# sensor_de_tension.net
KiCad netlist of a schematic drawn in Altium Designer
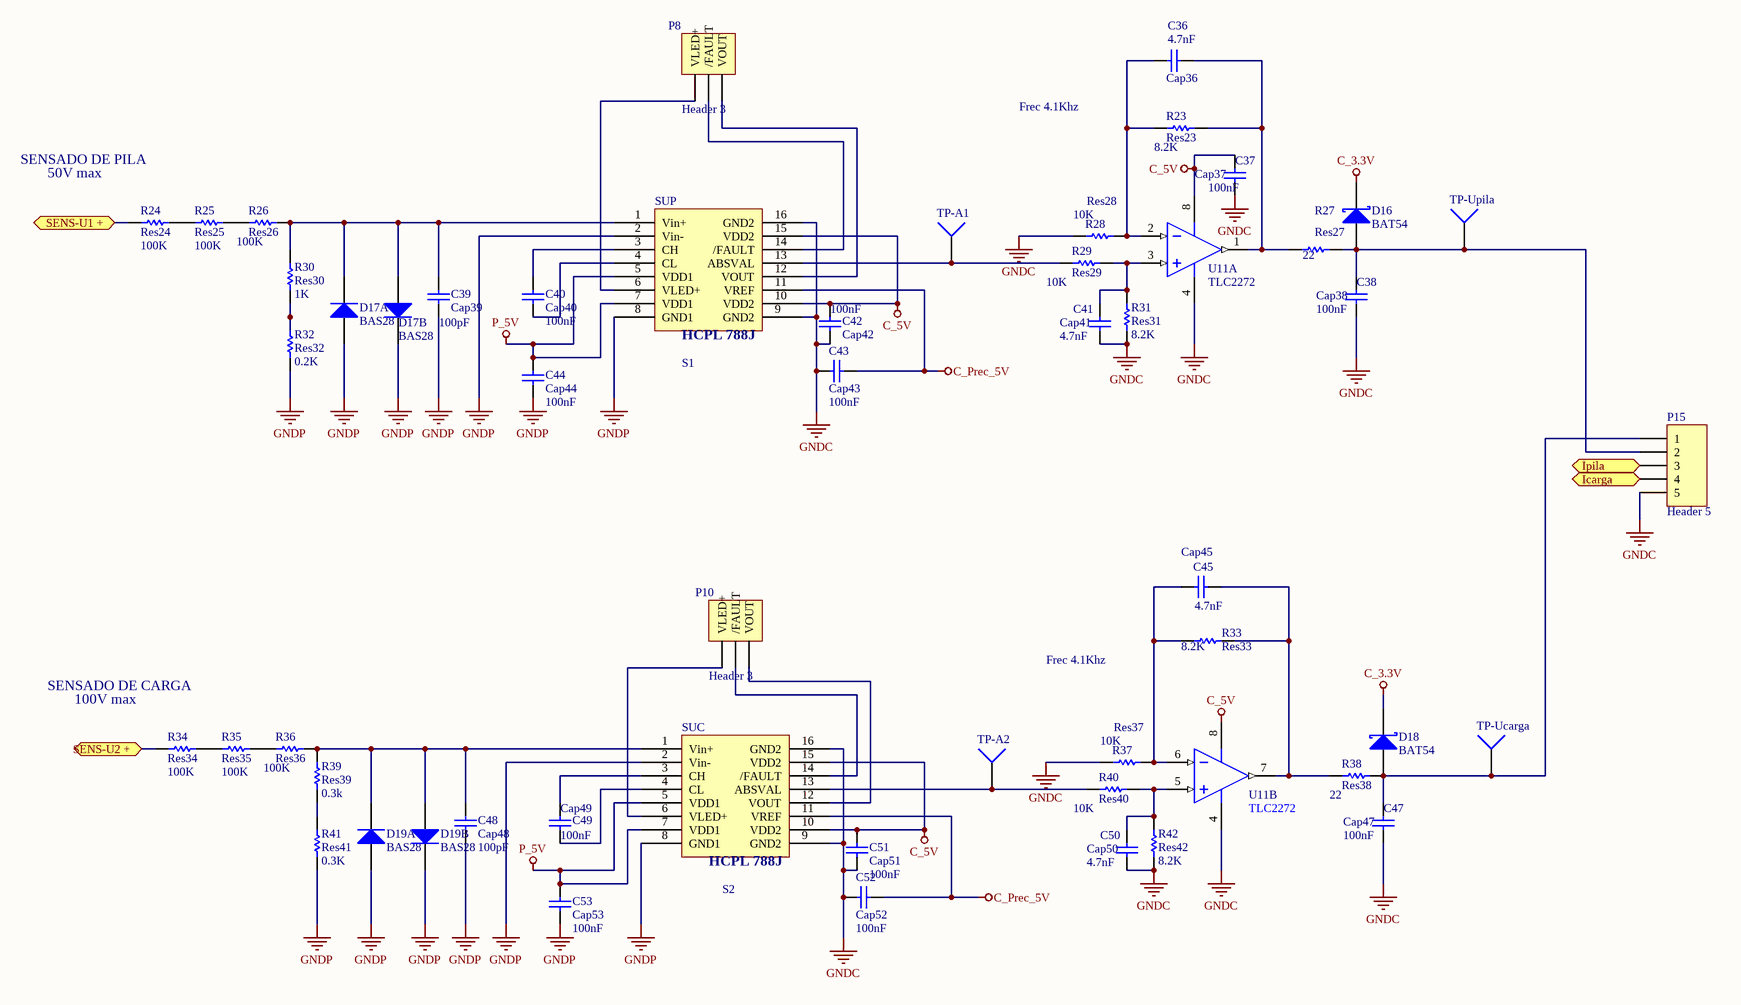
[diagram p0: sensor de tension.SchDoc]

(export (version "E")
  (design (tool "Eeschema 10.0.6"))
  (components
    (comp (ref "C36")
      (value "Cap36")
      (footprint "RAD-0.1")
      (description "THRU MULTICAPA 50V")
      (fields (field (name "ALTIUM_VALUE") "4.7nF") (field (name "PUBLISHER") "Altium Limited"))
      (libsource (lib "Miscellaneous Devices") (part "Cap"))
    )
    (comp (ref "C37")
      (value "Cap37")
      (footprint "8-1206")
      (description "SMD MULTICAPA 50V")
      (fields (field (name "ALTIUM_VALUE") "100nF") (field (name "PUBLISHER") "Altium Limited"))
      (libsource (lib "Miscellaneous Devices") (part "Cap"))
    )
    (comp (ref "C38")
      (value "Cap38")
      (footprint "8-1206")
      (description "SMD MULTICAPA 50V")
      (fields (field (name "ALTIUM_VALUE") "100nF") (field (name "PUBLISHER") "Altium Limited"))
      (libsource (lib "Miscellaneous Devices") (part "Cap"))
    )
    (comp (ref "C39")
      (value "Cap39")
      (footprint "8-1206")
      (description "SMD MULTICAPA 50V")
      (fields (field (name "ALTIUM_VALUE") "100pF") (field (name "PUBLISHER") "Altium Limited"))
      (libsource (lib "Miscellaneous Devices") (part "Cap"))
    )
    (comp (ref "C40")
      (value "Cap40")
      (footprint "8-1206")
      (description "SMD MULTICAPA 50V")
      (fields (field (name "ALTIUM_VALUE") "100nF") (field (name "PUBLISHER") "Altium Limited"))
      (libsource (lib "Miscellaneous Devices") (part "Cap"))
    )
    (comp (ref "C41")
      (value "Cap41")
      (footprint "RAD-0.1")
      (description "THRU MULTICAPA 50V")
      (fields (field (name "ALTIUM_VALUE") "4.7nF") (field (name "PUBLISHER") "Altium Limited"))
      (libsource (lib "Miscellaneous Devices") (part "Cap"))
    )
    (comp (ref "C42")
      (value "Cap42")
      (footprint "8-1206")
      (description "SMD MULTICAPA 50V")
      (fields (field (name "ALTIUM_VALUE") "100nF") (field (name "PUBLISHER") "Altium Limited"))
      (libsource (lib "Miscellaneous Devices") (part "Cap"))
    )
    (comp (ref "C43")
      (value "Cap43")
      (footprint "8-1206")
      (description "SMD MULTICAPA 50V")
      (fields (field (name "ALTIUM_VALUE") "100nF") (field (name "PUBLISHER") "Altium Limited"))
      (libsource (lib "Miscellaneous Devices") (part "Cap"))
    )
    (comp (ref "C44")
      (value "Cap44")
      (footprint "8-1206")
      (description "SMD MULTICAPA 50V")
      (fields (field (name "ALTIUM_VALUE") "100nF") (field (name "PUBLISHER") "Altium Limited"))
      (libsource (lib "Miscellaneous Devices") (part "Cap"))
    )
    (comp (ref "C45")
      (value "Cap45")
      (footprint "RAD-0.1")
      (description "THRU MULTICAPA 50V")
      (fields (field (name "ALTIUM_VALUE") "4.7nF") (field (name "PUBLISHER") "Altium Limited"))
      (libsource (lib "Miscellaneous Devices") (part "Cap"))
    )
    (comp (ref "C47")
      (value "Cap47")
      (footprint "8-1206")
      (description "SMD MULTICAPA 50V")
      (fields (field (name "ALTIUM_VALUE") "100nF") (field (name "PUBLISHER") "Altium Limited"))
      (libsource (lib "Miscellaneous Devices") (part "Cap"))
    )
    (comp (ref "C48")
      (value "Cap48")
      (footprint "8-1206")
      (description "SMD MULTICAPA 50V")
      (fields (field (name "ALTIUM_VALUE") "100pF") (field (name "PUBLISHER") "Altium Limited"))
      (libsource (lib "Miscellaneous Devices") (part "Cap"))
    )
    (comp (ref "C49")
      (value "Cap49")
      (footprint "8-1206")
      (description "SMD MULTICAPA 50V")
      (fields (field (name "ALTIUM_VALUE") "100nF") (field (name "PUBLISHER") "Altium Limited"))
      (libsource (lib "Miscellaneous Devices") (part "Cap"))
    )
    (comp (ref "C50")
      (value "Cap50")
      (footprint "RAD-0.1")
      (description "THRU MULTICAPA 50V")
      (fields (field (name "ALTIUM_VALUE") "4.7nF") (field (name "PUBLISHER") "Altium Limited"))
      (libsource (lib "Miscellaneous Devices") (part "Cap"))
    )
    (comp (ref "C51")
      (value "Cap51")
      (footprint "8-1206")
      (description "SMD MULTICAPA 50V")
      (fields (field (name "ALTIUM_VALUE") "100nF") (field (name "PUBLISHER") "Altium Limited"))
      (libsource (lib "Miscellaneous Devices") (part "Cap"))
    )
    (comp (ref "C52")
      (value "Cap52")
      (footprint "8-1206")
      (description "SMD MULTICAPA 50V")
      (fields (field (name "ALTIUM_VALUE") "100nF") (field (name "PUBLISHER") "Altium Limited"))
      (libsource (lib "Miscellaneous Devices") (part "Cap"))
    )
    (comp (ref "C53")
      (value "Cap53")
      (footprint "8-1206")
      (description "SMD MULTICAPA 50V")
      (fields (field (name "ALTIUM_VALUE") "100nF") (field (name "PUBLISHER") "Altium Limited"))
      (libsource (lib "Miscellaneous Devices") (part "Cap"))
    )
    (comp (ref "D16")
      (value "BAT54")
      (footprint "SOD123*")
      (description "SMD")
      (fields (field (name "PUBLISHER") "Altium Limited"))
      (libsource (lib "Philips Discrete Diode - Schottky") (part "BAT54"))
    )
    (comp (ref "D17")
      (value "BAS28")
      (footprint "SOT-143*")
      (description "SMD")
      (fields (field (name "PUBLISHER") "Altium Limited"))
      (libsource (lib "Philips Discrete Diode - Switching") (part "BAS28"))
    )
    (comp (ref "D18")
      (value "BAT54")
      (footprint "SOD123*")
      (description "SMD")
      (fields (field (name "PUBLISHER") "Altium Limited"))
      (libsource (lib "Philips Discrete Diode - Schottky") (part "BAT54"))
    )
    (comp (ref "D19")
      (value "BAS28")
      (footprint "SOT-143*")
      (description "High-speed Switching, Double Diode SMD")
      (fields (field (name "PUBLISHER") "Altium Limited"))
      (libsource (lib "Philips Discrete Diode - Switching") (part "BAS28"))
    )
    (comp (ref "P8")
      (value "Header 3")
      (footprint "HDR1X3*")
      (description "Header, 3-Pin")
      (fields (field (name "PUBLISHER") "Altium Limited"))
      (libsource (lib "Miscellaneous Connectors") (part "Header 3"))
    )
    (comp (ref "P10")
      (value "Header 3")
      (footprint "HDR1X3*")
      (description "Header, 3-Pin")
      (fields (field (name "PUBLISHER") "Altium Limited"))
      (libsource (lib "Miscellaneous Connectors") (part "Header 3"))
    )
    (comp (ref "P15")
      (value "Header 5")
      (footprint "HDR1X5H*")
      (description "Header, 5-Pin")
      (fields (field (name "PUBLISHER") "Altium Limited"))
      (libsource (lib "Miscellaneous Connectors") (part "Header 5"))
    )
    (comp (ref "R23")
      (value "Res23")
      (footprint "AXIAL-0.4")
      (description "Resistor")
      (fields (field (name "ALTIUM_VALUE") "8.2K") (field (name "PUBLISHER") "Altium Limited"))
      (libsource (lib "Miscellaneous Devices") (part "Res1"))
    )
    (comp (ref "R24")
      (value "Res24")
      (footprint "8-1206")
      (description "SMD 1206")
      (fields (field (name "ALTIUM_VALUE") "100K") (field (name "PUBLISHER") "Altium Limited"))
      (libsource (lib "Miscellaneous Devices") (part "Res1"))
    )
    (comp (ref "R25")
      (value "Res25")
      (footprint "8-1206")
      (description "SMD 1206")
      (fields (field (name "ALTIUM_VALUE") "100K") (field (name "PUBLISHER") "Altium Limited"))
      (libsource (lib "Miscellaneous Devices") (part "Res1"))
    )
    (comp (ref "R26")
      (value "Res26")
      (footprint "8-1206")
      (description "SMD 1206")
      (fields (field (name "ALTIUM_VALUE") "100K") (field (name "PUBLISHER") "Altium Limited"))
      (libsource (lib "Miscellaneous Devices") (part "Res1"))
    )
    (comp (ref "R27")
      (value "Res27")
      (footprint "8-1206")
      (description "SMD 1206")
      (fields (field (name "ALTIUM_VALUE") "22") (field (name "PUBLISHER") "Altium Limited"))
      (libsource (lib "Miscellaneous Devices") (part "Res1"))
    )
    (comp (ref "R28")
      (value "Res28")
      (footprint "AXIAL-0.4")
      (description "Resistor")
      (fields (field (name "ALTIUM_VALUE") "10K") (field (name "PUBLISHER") "Altium Limited"))
      (libsource (lib "Miscellaneous Devices") (part "Res1"))
    )
    (comp (ref "R29")
      (value "Res29")
      (footprint "AXIAL-0.4")
      (description "Resistor")
      (fields (field (name "ALTIUM_VALUE") "10K") (field (name "PUBLISHER") "Altium Limited"))
      (libsource (lib "Miscellaneous Devices") (part "Res1"))
    )
    (comp (ref "R30")
      (value "Res30")
      (footprint "AXIAL-0.4")
      (description "Resistor")
      (fields (field (name "ALTIUM_VALUE") "1K") (field (name "PUBLISHER") "Altium Limited"))
      (libsource (lib "Miscellaneous Devices") (part "Res1"))
    )
    (comp (ref "R31")
      (value "Res31")
      (footprint "AXIAL-0.4")
      (description "Resistor")
      (fields (field (name "ALTIUM_VALUE") "8.2K") (field (name "PUBLISHER") "Altium Limited"))
      (libsource (lib "Miscellaneous Devices") (part "Res1"))
    )
    (comp (ref "R32")
      (value "Res32")
      (footprint "AXIAL-0.4")
      (description "Resistor")
      (fields (field (name "ALTIUM_VALUE") "0.2K") (field (name "PUBLISHER") "Altium Limited"))
      (libsource (lib "Miscellaneous Devices") (part "Res1"))
    )
    (comp (ref "R33")
      (value "Res33")
      (footprint "AXIAL-0.4")
      (description "Resistor")
      (fields (field (name "ALTIUM_VALUE") "8.2K") (field (name "PUBLISHER") "Altium Limited"))
      (libsource (lib "Miscellaneous Devices") (part "Res1"))
    )
    (comp (ref "R34")
      (value "Res34")
      (footprint "8-1206")
      (description "SMD 1206")
      (fields (field (name "ALTIUM_VALUE") "100K") (field (name "PUBLISHER") "Altium Limited"))
      (libsource (lib "Miscellaneous Devices") (part "Res1"))
    )
    (comp (ref "R35")
      (value "Res35")
      (footprint "8-1206")
      (description "SMD 1206")
      (fields (field (name "ALTIUM_VALUE") "100K") (field (name "PUBLISHER") "Altium Limited"))
      (libsource (lib "Miscellaneous Devices") (part "Res1"))
    )
    (comp (ref "R36")
      (value "Res36")
      (footprint "8-1206")
      (description "SMD 1206")
      (fields (field (name "ALTIUM_VALUE") "100K") (field (name "PUBLISHER") "Altium Limited"))
      (libsource (lib "Miscellaneous Devices") (part "Res1"))
    )
    (comp (ref "R37")
      (value "Res37")
      (footprint "AXIAL-0.4")
      (description "Resistor")
      (fields (field (name "ALTIUM_VALUE") "10K") (field (name "PUBLISHER") "Altium Limited"))
      (libsource (lib "Miscellaneous Devices") (part "Res1"))
    )
    (comp (ref "R38")
      (value "Res38")
      (footprint "8-1206")
      (description "SMD 1206")
      (fields (field (name "ALTIUM_VALUE") "22") (field (name "PUBLISHER") "Altium Limited"))
      (libsource (lib "Miscellaneous Devices") (part "Res1"))
    )
    (comp (ref "R39")
      (value "Res39")
      (footprint "AXIAL-0.4")
      (description "Resistor")
      (fields (field (name "ALTIUM_VALUE") "0.3k") (field (name "PUBLISHER") "Altium Limited"))
      (libsource (lib "Miscellaneous Devices") (part "Res1"))
    )
    (comp (ref "R40")
      (value "Res40")
      (footprint "AXIAL-0.4")
      (description "Resistor")
      (fields (field (name "ALTIUM_VALUE") "10K") (field (name "PUBLISHER") "Altium Limited"))
      (libsource (lib "Miscellaneous Devices") (part "Res1"))
    )
    (comp (ref "R41")
      (value "Res41")
      (footprint "AXIAL-0.4")
      (description "Resistor")
      (fields (field (name "ALTIUM_VALUE") "0.3K") (field (name "PUBLISHER") "Altium Limited"))
      (libsource (lib "Miscellaneous Devices") (part "Res1"))
    )
    (comp (ref "R42")
      (value "Res42")
      (footprint "AXIAL-0.4")
      (description "Resistor")
      (fields (field (name "ALTIUM_VALUE") "8.2K") (field (name "PUBLISHER") "Altium Limited"))
      (libsource (lib "Miscellaneous Devices") (part "Res1"))
    )
    (comp (ref "SUC")
      (value "S2")
      (footprint "Sens Tension HCPL-788J")
      (libsource (lib "sensor tension HCPL 788J") (part "Component_1"))
    )
    (comp (ref "SUP")
      (value "S1")
      (footprint "Sens Tension HCPL-788J")
      (libsource (lib "sensor tension HCPL 788J") (part "Component_1"))
    )
    (comp (ref "TP-A1")
      (value "~")
      (footprint "PIN1")
      (description "Socket")
      (fields (field (name "PUBLISHER") "Altium Limited"))
      (libsource (lib "Miscellaneous Connectors") (part "Socket"))
    )
    (comp (ref "TP-A2")
      (value "~")
      (footprint "PIN1")
      (description "Socket")
      (fields (field (name "PUBLISHER") "Altium Limited"))
      (libsource (lib "Miscellaneous Connectors") (part "Socket"))
    )
    (comp (ref "TP-Ucarga")
      (value "~")
      (footprint "PIN1")
      (description "Socket")
      (fields (field (name "PUBLISHER") "Altium Limited"))
      (libsource (lib "Miscellaneous Connectors") (part "Socket"))
    )
    (comp (ref "TP-Upila")
      (value "~")
      (footprint "PIN1")
      (description "Socket")
      (fields (field (name "PUBLISHER") "Altium Limited"))
      (libsource (lib "Miscellaneous Connectors") (part "Socket"))
    )
    (comp (ref "U11")
      (value "TLC2272")
      (footprint "751-02_N")
      (description "LinCMOS Precision Dual Operational Amplifier")
      (fields (field (name "PUBLISHER") "Altium Limited"))
      (libsource (lib "TI Operational Amplifier") (part "TLC27L2ACDR"))
    )
  )
  (nets
    (net (code "1") (name "/Icarga") (class "Default")
      (node (ref "P15") (pin "4") (pinfunction "4_4") (pintype "passive"))
    )
    (net (code "2") (name "/Ipila") (class "Default")
      (node (ref "P15") (pin "3") (pinfunction "3_3") (pintype "passive"))
    )
    (net (code "3") (name "/SENS-U1 +") (class "Default")
      (node (ref "R24") (pin "1") (pinfunction "1_1") (pintype "passive"))
    )
    (net (code "4") (name "/SENS-U2 +") (class "Default")
      (node (ref "R34") (pin "1") (pinfunction "1_1") (pintype "passive"))
    )
    (net (code "5") (name "C_3.3V") (class "Default")
      (node (ref "D16") (pin "2") (pinfunction "K_2") (pintype "passive"))
      (node (ref "D18") (pin "2") (pinfunction "K_2") (pintype "passive"))
    )
    (net (code "6") (name "C_5V") (class "Default")
      (node (ref "C37") (pin "1") (pinfunction "1_1") (pintype "passive"))
      (node (ref "C42") (pin "2") (pinfunction "2_2") (pintype "passive"))
      (node (ref "C51") (pin "2") (pinfunction "2_2") (pintype "passive"))
      (node (ref "SUC") (pin "10") (pinfunction "VDD2_10") (pintype "passive"))
      (node (ref "SUC") (pin "15") (pinfunction "VDD2_15") (pintype "passive"))
      (node (ref "SUP") (pin "10") (pinfunction "VDD2_10") (pintype "passive"))
      (node (ref "SUP") (pin "15") (pinfunction "VDD2_15") (pintype "passive"))
      (node (ref "U11") (pin "8") (pinfunction "VDD_8") (pintype "power_in"))
    )
    (net (code "7") (name "C_Prec_5V") (class "Default")
      (node (ref "C43") (pin "2") (pinfunction "2_2") (pintype "passive"))
      (node (ref "C52") (pin "2") (pinfunction "2_2") (pintype "passive"))
      (node (ref "SUC") (pin "11") (pinfunction "VREF_11") (pintype "passive"))
      (node (ref "SUP") (pin "11") (pinfunction "VREF_11") (pintype "passive"))
    )
    (net (code "8") (name "GNDC") (class "Default")
      (node (ref "C37") (pin "2") (pinfunction "2_2") (pintype "passive"))
      (node (ref "C38") (pin "2") (pinfunction "2_2") (pintype "passive"))
      (node (ref "C41") (pin "2") (pinfunction "2_2") (pintype "passive"))
      (node (ref "C42") (pin "1") (pinfunction "1_1") (pintype "passive"))
      (node (ref "C43") (pin "1") (pinfunction "1_1") (pintype "passive"))
      (node (ref "C47") (pin "2") (pinfunction "2_2") (pintype "passive"))
      (node (ref "C50") (pin "2") (pinfunction "2_2") (pintype "passive"))
      (node (ref "C51") (pin "1") (pinfunction "1_1") (pintype "passive"))
      (node (ref "C52") (pin "1") (pinfunction "1_1") (pintype "passive"))
      (node (ref "P15") (pin "5") (pinfunction "5_5") (pintype "passive"))
      (node (ref "R28") (pin "1") (pinfunction "1_1") (pintype "passive"))
      (node (ref "R31") (pin "2") (pinfunction "2_2") (pintype "passive"))
      (node (ref "R37") (pin "1") (pinfunction "1_1") (pintype "passive"))
      (node (ref "R42") (pin "2") (pinfunction "2_2") (pintype "passive"))
      (node (ref "SUC") (pin "16") (pinfunction "GND2_16") (pintype "passive"))
      (node (ref "SUC") (pin "9") (pinfunction "GND2_9") (pintype "passive"))
      (node (ref "SUP") (pin "16") (pinfunction "GND2_16") (pintype "passive"))
      (node (ref "SUP") (pin "9") (pinfunction "GND2_9") (pintype "passive"))
      (node (ref "U11") (pin "4") (pinfunction "GND_4") (pintype "power_in"))
    )
    (net (code "9") (name "GNDP") (class "Default")
      (node (ref "C39") (pin "2") (pinfunction "2_2") (pintype "passive"))
      (node (ref "C44") (pin "2") (pinfunction "2_2") (pintype "passive"))
      (node (ref "C48") (pin "2") (pinfunction "2_2") (pintype "passive"))
      (node (ref "C53") (pin "2") (pinfunction "2_2") (pintype "passive"))
      (node (ref "D17") (pin "2") (pinfunction "K_2") (pintype "passive"))
      (node (ref "D17") (pin "4") (pinfunction "A_4") (pintype "passive"))
      (node (ref "D19") (pin "2") (pinfunction "K_2") (pintype "passive"))
      (node (ref "D19") (pin "4") (pinfunction "A_4") (pintype "passive"))
      (node (ref "R32") (pin "2") (pinfunction "2_2") (pintype "passive"))
      (node (ref "R41") (pin "2") (pinfunction "2_2") (pintype "passive"))
      (node (ref "SUC") (pin "2") (pinfunction "Vin-_2") (pintype "passive"))
      (node (ref "SUC") (pin "8") (pinfunction "GND1_8") (pintype "passive"))
      (node (ref "SUP") (pin "2") (pinfunction "Vin-_2") (pintype "passive"))
      (node (ref "SUP") (pin "8") (pinfunction "GND1_8") (pintype "passive"))
    )
    (net (code "10") (name "Net-(D16-A)") (class "Default")
      (node (ref "C38") (pin "1") (pinfunction "1_1") (pintype "passive"))
      (node (ref "D16") (pin "1") (pinfunction "A_1") (pintype "passive"))
      (node (ref "P15") (pin "2") (pinfunction "2_2") (pintype "passive"))
      (node (ref "R27") (pin "2") (pinfunction "2_2") (pintype "passive"))
      (node (ref "TP-Upila") (pin "1") (pinfunction "1_1") (pintype "passive"))
    )
    (net (code "11") (name "Net-(D17A-K)") (class "Default")
      (node (ref "C39") (pin "1") (pinfunction "1_1") (pintype "passive"))
      (node (ref "D17") (pin "1") (pinfunction "K_1") (pintype "passive"))
      (node (ref "D17") (pin "3") (pinfunction "A_3") (pintype "passive"))
      (node (ref "R26") (pin "2") (pinfunction "2_2") (pintype "passive"))
      (node (ref "R30") (pin "1") (pinfunction "1_1") (pintype "passive"))
      (node (ref "SUP") (pin "1") (pinfunction "Vin+_1") (pintype "passive"))
    )
    (net (code "12") (name "Net-(D18-A)") (class "Default")
      (node (ref "C47") (pin "1") (pinfunction "1_1") (pintype "passive"))
      (node (ref "D18") (pin "1") (pinfunction "A_1") (pintype "passive"))
      (node (ref "P15") (pin "1") (pinfunction "1_1") (pintype "passive"))
      (node (ref "R38") (pin "2") (pinfunction "2_2") (pintype "passive"))
      (node (ref "TP-Ucarga") (pin "1") (pinfunction "1_1") (pintype "passive"))
    )
    (net (code "13") (name "Net-(D19A-K)") (class "Default")
      (node (ref "C48") (pin "1") (pinfunction "1_1") (pintype "passive"))
      (node (ref "D19") (pin "1") (pinfunction "K_1") (pintype "passive"))
      (node (ref "D19") (pin "3") (pinfunction "A_3") (pintype "passive"))
      (node (ref "R36") (pin "2") (pinfunction "2_2") (pintype "passive"))
      (node (ref "R39") (pin "1") (pinfunction "1_1") (pintype "passive"))
      (node (ref "SUC") (pin "1") (pinfunction "Vin+_1") (pintype "passive"))
    )
    (net (code "14") (name "Net-(P8-VLED+)") (class "Default")
      (node (ref "P8") (pin "1") (pinfunction "VLED+_1") (pintype "passive"))
      (node (ref "SUP") (pin "6") (pinfunction "VLED+_6") (pintype "passive"))
    )
    (net (code "15") (name "Net-(P8-VOUT)") (class "Default")
      (node (ref "P8") (pin "3") (pinfunction "VOUT_3") (pintype "passive"))
      (node (ref "SUP") (pin "12") (pinfunction "VOUT_12") (pintype "passive"))
    )
    (net (code "16") (name "Net-(P8-{slash}FAULT)") (class "Default")
      (node (ref "P8") (pin "2") (pinfunction "/FAULT_2") (pintype "passive"))
      (node (ref "SUP") (pin "14") (pinfunction "/FAULT_14") (pintype "passive"))
    )
    (net (code "17") (name "Net-(P10-VLED+)") (class "Default")
      (node (ref "P10") (pin "1") (pinfunction "VLED+_1") (pintype "passive"))
      (node (ref "SUC") (pin "6") (pinfunction "VLED+_6") (pintype "passive"))
    )
    (net (code "18") (name "Net-(P10-VOUT)") (class "Default")
      (node (ref "P10") (pin "3") (pinfunction "VOUT_3") (pintype "passive"))
      (node (ref "SUC") (pin "12") (pinfunction "VOUT_12") (pintype "passive"))
    )
    (net (code "19") (name "Net-(P10-{slash}FAULT)") (class "Default")
      (node (ref "P10") (pin "2") (pinfunction "/FAULT_2") (pintype "passive"))
      (node (ref "SUC") (pin "14") (pinfunction "/FAULT_14") (pintype "passive"))
    )
    (net (code "20") (name "Net-(R24-Pad2)") (class "Default")
      (node (ref "R24") (pin "2") (pinfunction "2_2") (pintype "passive"))
      (node (ref "R25") (pin "1") (pinfunction "1_1") (pintype "passive"))
    )
    (net (code "21") (name "Net-(R25-Pad2)") (class "Default")
      (node (ref "R25") (pin "2") (pinfunction "2_2") (pintype "passive"))
      (node (ref "R26") (pin "1") (pinfunction "1_1") (pintype "passive"))
    )
    (net (code "22") (name "Net-(R30-Pad2)") (class "Default")
      (node (ref "R30") (pin "2") (pinfunction "2_2") (pintype "passive"))
      (node (ref "R32") (pin "1") (pinfunction "1_1") (pintype "passive"))
    )
    (net (code "23") (name "Net-(R34-Pad2)") (class "Default")
      (node (ref "R34") (pin "2") (pinfunction "2_2") (pintype "passive"))
      (node (ref "R35") (pin "1") (pinfunction "1_1") (pintype "passive"))
    )
    (net (code "24") (name "Net-(R35-Pad2)") (class "Default")
      (node (ref "R35") (pin "2") (pinfunction "2_2") (pintype "passive"))
      (node (ref "R36") (pin "1") (pinfunction "1_1") (pintype "passive"))
    )
    (net (code "25") (name "Net-(R39-Pad2)") (class "Default")
      (node (ref "R39") (pin "2") (pinfunction "2_2") (pintype "passive"))
      (node (ref "R41") (pin "1") (pinfunction "1_1") (pintype "passive"))
    )
    (net (code "26") (name "Net-(SUC-ABSVAL)") (class "Default")
      (node (ref "R40") (pin "1") (pinfunction "1_1") (pintype "passive"))
      (node (ref "SUC") (pin "13") (pinfunction "ABSVAL_13") (pintype "passive"))
      (node (ref "TP-A2") (pin "1") (pinfunction "1_1") (pintype "passive"))
    )
    (net (code "27") (name "Net-(SUC-CH)") (class "Default")
      (node (ref "C49") (pin "1") (pinfunction "1_1") (pintype "passive"))
      (node (ref "SUC") (pin "3") (pinfunction "CH_3") (pintype "passive"))
    )
    (net (code "28") (name "Net-(SUC-CL)") (class "Default")
      (node (ref "C49") (pin "2") (pinfunction "2_2") (pintype "passive"))
      (node (ref "SUC") (pin "4") (pinfunction "CL_4") (pintype "passive"))
    )
    (net (code "29") (name "Net-(SUP-ABSVAL)") (class "Default")
      (node (ref "R29") (pin "1") (pinfunction "1_1") (pintype "passive"))
      (node (ref "SUP") (pin "13") (pinfunction "ABSVAL_13") (pintype "passive"))
      (node (ref "TP-A1") (pin "1") (pinfunction "1_1") (pintype "passive"))
    )
    (net (code "30") (name "Net-(SUP-CH)") (class "Default")
      (node (ref "C40") (pin "1") (pinfunction "1_1") (pintype "passive"))
      (node (ref "SUP") (pin "3") (pinfunction "CH_3") (pintype "passive"))
    )
    (net (code "31") (name "Net-(SUP-CL)") (class "Default")
      (node (ref "C40") (pin "2") (pinfunction "2_2") (pintype "passive"))
      (node (ref "SUP") (pin "4") (pinfunction "CL_4") (pintype "passive"))
    )
    (net (code "32") (name "Net-(U11A-IN+)") (class "Default")
      (node (ref "C41") (pin "1") (pinfunction "1_1") (pintype "passive"))
      (node (ref "R29") (pin "2") (pinfunction "2_2") (pintype "passive"))
      (node (ref "R31") (pin "1") (pinfunction "1_1") (pintype "passive"))
      (node (ref "U11") (pin "3") (pinfunction "IN+_3") (pintype "input"))
    )
    (net (code "33") (name "Net-(U11A-IN-)") (class "Default")
      (node (ref "C36") (pin "1") (pinfunction "1_1") (pintype "passive"))
      (node (ref "R23") (pin "1") (pinfunction "1_1") (pintype "passive"))
      (node (ref "R28") (pin "2") (pinfunction "2_2") (pintype "passive"))
      (node (ref "U11") (pin "2") (pinfunction "IN-_2") (pintype "input"))
    )
    (net (code "34") (name "Net-(U11A-OUT)") (class "Default")
      (node (ref "C36") (pin "2") (pinfunction "2_2") (pintype "passive"))
      (node (ref "R23") (pin "2") (pinfunction "2_2") (pintype "passive"))
      (node (ref "R27") (pin "1") (pinfunction "1_1") (pintype "passive"))
      (node (ref "U11") (pin "1") (pinfunction "OUT_1") (pintype "output"))
    )
    (net (code "35") (name "Net-(U11B-IN+)") (class "Default")
      (node (ref "C50") (pin "1") (pinfunction "1_1") (pintype "passive"))
      (node (ref "R40") (pin "2") (pinfunction "2_2") (pintype "passive"))
      (node (ref "R42") (pin "1") (pinfunction "1_1") (pintype "passive"))
      (node (ref "U11") (pin "5") (pinfunction "IN+_5") (pintype "input"))
    )
    (net (code "36") (name "Net-(U11B-IN-)") (class "Default")
      (node (ref "C45") (pin "1") (pinfunction "1_1") (pintype "passive"))
      (node (ref "R33") (pin "1") (pinfunction "1_1") (pintype "passive"))
      (node (ref "R37") (pin "2") (pinfunction "2_2") (pintype "passive"))
      (node (ref "U11") (pin "6") (pinfunction "IN-_6") (pintype "input"))
    )
    (net (code "37") (name "Net-(U11B-OUT)") (class "Default")
      (node (ref "C45") (pin "2") (pinfunction "2_2") (pintype "passive"))
      (node (ref "R33") (pin "2") (pinfunction "2_2") (pintype "passive"))
      (node (ref "R38") (pin "1") (pinfunction "1_1") (pintype "passive"))
      (node (ref "U11") (pin "7") (pinfunction "OUT_7") (pintype "output"))
    )
    (net (code "38") (name "P_5V") (class "Default")
      (node (ref "C44") (pin "1") (pinfunction "1_1") (pintype "passive"))
      (node (ref "C53") (pin "1") (pinfunction "1_1") (pintype "passive"))
      (node (ref "SUC") (pin "5") (pinfunction "VDD1_5") (pintype "passive"))
      (node (ref "SUC") (pin "7") (pinfunction "VDD1_7") (pintype "passive"))
      (node (ref "SUP") (pin "5") (pinfunction "VDD1_5") (pintype "passive"))
      (node (ref "SUP") (pin "7") (pinfunction "VDD1_7") (pintype "passive"))
    )
  )
)
